# kingoftone_v2.net
KiCad netlist of a schematic drawn in EAGLE
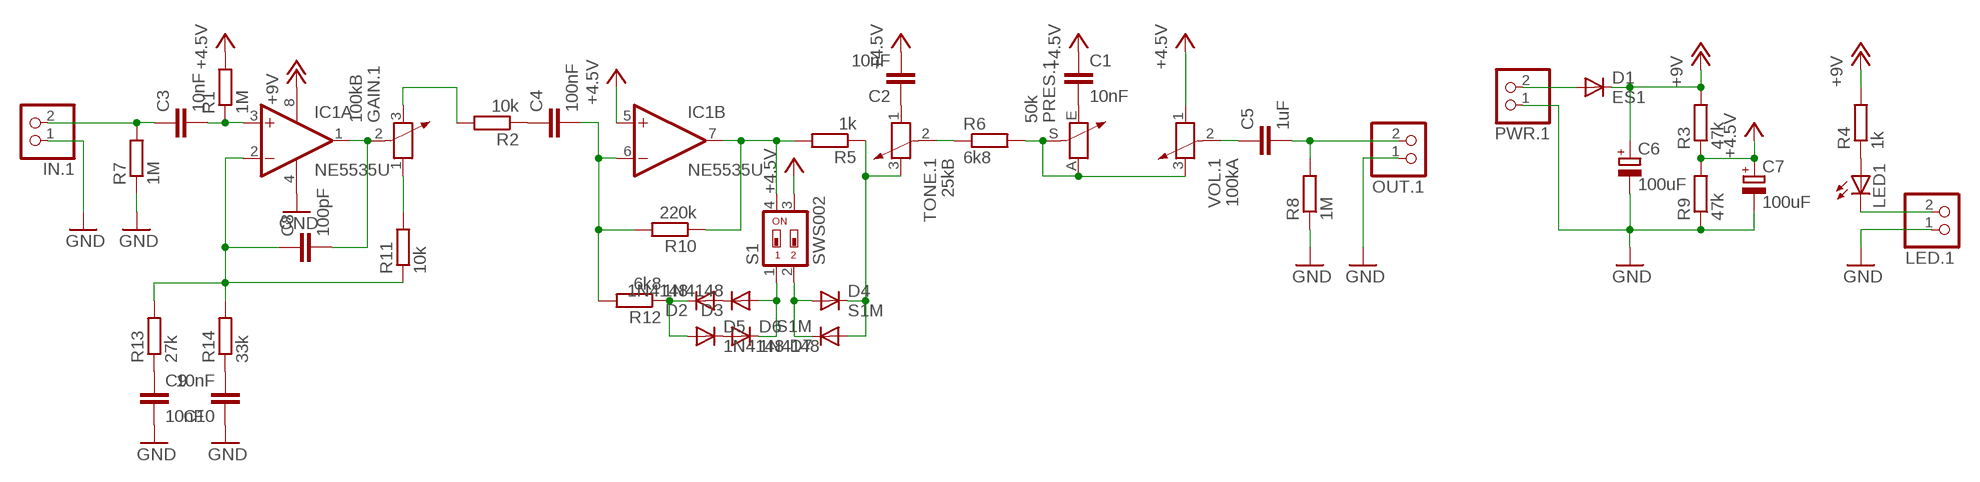
[diagram p0: schematic, sheet 1]

(export (version "E")
  (design (tool "Eeschema 10.0.6"))
  (components
    (comp (ref "C1")
      (value "10nF")
      (footprint "eagle-import:C0805K")
      (libsource (lib "eagle-import") (part "C-EUC0805K"))
    )
    (comp (ref "C2")
      (value "10nF")
      (footprint "eagle-import:C0805K")
      (libsource (lib "eagle-import") (part "C-EUC0805K"))
    )
    (comp (ref "C3")
      (value "10nF")
      (footprint "eagle-import:C0805K")
      (libsource (lib "eagle-import") (part "C-EUC0805K"))
    )
    (comp (ref "C4")
      (value "100nF")
      (footprint "eagle-import:C0805K")
      (libsource (lib "eagle-import") (part "C-EUC0805K"))
    )
    (comp (ref "C5")
      (value "1uF")
      (footprint "eagle-import:C0805K")
      (libsource (lib "eagle-import") (part "C-EUC0805K"))
    )
    (comp (ref "C6")
      (value "100uF")
      (footprint "eagle-import:PANASONIC_D")
      (libsource (lib "eagle-import") (part "CPOL-EUD"))
    )
    (comp (ref "C7")
      (value "100uF")
      (footprint "eagle-import:PANASONIC_D")
      (libsource (lib "eagle-import") (part "CPOL-EUD"))
    )
    (comp (ref "C8")
      (value "100pF")
      (footprint "eagle-import:C0805K")
      (libsource (lib "eagle-import") (part "C-EUC0805K"))
    )
    (comp (ref "C9")
      (value "10nF")
      (footprint "eagle-import:C0805K")
      (libsource (lib "eagle-import") (part "C-EUC0805K"))
    )
    (comp (ref "C10")
      (value "10nF")
      (footprint "eagle-import:C0805K")
      (libsource (lib "eagle-import") (part "C-EUC0805K"))
    )
    (comp (ref "D1")
      (value "ES1")
      (footprint "eagle-import:DO-214AC")
      (libsource (lib "eagle-import") (part "ES1"))
    )
    (comp (ref "D2")
      (value "1N4148")
      (footprint "eagle-import:D0805")
      (libsource (lib "eagle-import") (part "1N4148"))
    )
    (comp (ref "D3")
      (value "1N4148")
      (footprint "eagle-import:D0805")
      (libsource (lib "eagle-import") (part "1N4148"))
    )
    (comp (ref "D4")
      (value "S1M")
      (footprint "eagle-import:DO-214AC")
      (libsource (lib "eagle-import") (part "S1M"))
    )
    (comp (ref "D5")
      (value "1N4148")
      (footprint "eagle-import:D0805")
      (libsource (lib "eagle-import") (part "1N4148"))
    )
    (comp (ref "D6")
      (value "1N4148")
      (footprint "eagle-import:D0805")
      (libsource (lib "eagle-import") (part "1N4148"))
    )
    (comp (ref "D7")
      (value "S1M")
      (footprint "eagle-import:DO-214AC")
      (libsource (lib "eagle-import") (part "S1M"))
    )
    (comp (ref "GAIN.1")
      (value "100kB")
      (footprint "eagle-import:1X03")
      (libsource (lib "eagle-import") (part "POTENTIOMETER_"))
    )
    (comp (ref "IC1")
      (value "NE5535U")
      (footprint "eagle-import:SO08")
      (libsource (lib "eagle-import") (part "NE5535U"))
    )
    (comp (ref "IN.1")
      (value "PINHD-1X2")
      (footprint "eagle-import:1X02")
      (libsource (lib "eagle-import") (part "PINHD-1X2"))
    )
    (comp (ref "LED.1")
      (value "PINHD-1X2")
      (footprint "eagle-import:1X02")
      (libsource (lib "eagle-import") (part "PINHD-1X2"))
    )
    (comp (ref "LED1")
      (value "LED3MM")
      (footprint "eagle-import:LED3MM")
      (libsource (lib "eagle-import") (part "LED3MM"))
    )
    (comp (ref "OUT.1")
      (value "PINHD-1X2")
      (footprint "eagle-import:1X02")
      (libsource (lib "eagle-import") (part "PINHD-1X2"))
    )
    (comp (ref "PRES.1")
      (value "50k")
      (footprint "eagle-import:CT6")
      (libsource (lib "eagle-import") (part "POTENTIOMETER_CT6"))
    )
    (comp (ref "PWR.1")
      (value "PINHD-1X2")
      (footprint "eagle-import:1X02")
      (libsource (lib "eagle-import") (part "PINHD-1X2"))
    )
    (comp (ref "R1")
      (value "1M")
      (footprint "eagle-import:R0805")
      (libsource (lib "eagle-import") (part "R-EU_0805"))
    )
    (comp (ref "R2")
      (value "10k")
      (footprint "eagle-import:R0805")
      (libsource (lib "eagle-import") (part "R-EU_0805"))
    )
    (comp (ref "R3")
      (value "47k")
      (footprint "eagle-import:R0805")
      (libsource (lib "eagle-import") (part "R-EU_0805"))
    )
    (comp (ref "R4")
      (value "1k")
      (footprint "eagle-import:R0805")
      (libsource (lib "eagle-import") (part "R-EU_0805"))
    )
    (comp (ref "R5")
      (value "1k")
      (footprint "eagle-import:R0805")
      (libsource (lib "eagle-import") (part "R-EU_0805"))
    )
    (comp (ref "R6")
      (value "6k8")
      (footprint "eagle-import:R0805")
      (libsource (lib "eagle-import") (part "R-EU_0805"))
    )
    (comp (ref "R7")
      (value "1M")
      (footprint "eagle-import:R0805")
      (libsource (lib "eagle-import") (part "R-EU_0805"))
    )
    (comp (ref "R8")
      (value "1M")
      (footprint "eagle-import:R0805")
      (libsource (lib "eagle-import") (part "R-EU_0805"))
    )
    (comp (ref "R9")
      (value "47k")
      (footprint "eagle-import:R0805")
      (libsource (lib "eagle-import") (part "R-EU_0805"))
    )
    (comp (ref "R10")
      (value "220k")
      (footprint "eagle-import:R0805")
      (libsource (lib "eagle-import") (part "R-EU_0805"))
    )
    (comp (ref "R11")
      (value "10k")
      (footprint "eagle-import:R0805")
      (libsource (lib "eagle-import") (part "R-EU_0805"))
    )
    (comp (ref "R12")
      (value "6k8")
      (footprint "eagle-import:R0805")
      (libsource (lib "eagle-import") (part "R-EU_0805"))
    )
    (comp (ref "R13")
      (value "27k")
      (footprint "eagle-import:R0805")
      (libsource (lib "eagle-import") (part "R-EU_0805"))
    )
    (comp (ref "R14")
      (value "33k")
      (footprint "eagle-import:R0805")
      (libsource (lib "eagle-import") (part "R-EU_0805"))
    )
    (comp (ref "S1")
      (value "SWS002")
      (footprint "eagle-import:SMS-002")
      (libsource (lib "eagle-import") (part "SWS002"))
    )
    (comp (ref "TONE.1")
      (value "25kB")
      (footprint "eagle-import:1X03")
      (libsource (lib "eagle-import") (part "POTENTIOMETER_"))
    )
    (comp (ref "VOL.1")
      (value "100kA")
      (footprint "eagle-import:1X03")
      (libsource (lib "eagle-import") (part "POTENTIOMETER_"))
    )
  )
  (nets
    (net (code "1") (name "+4.5V") (class "Default")
      (node (ref "C1") (pin "1") (pinfunction "1_1") (pintype "passive"))
      (node (ref "C2") (pin "2") (pinfunction "2_2") (pintype "passive"))
      (node (ref "C7") (pin "+") (pinfunction "+_+") (pintype "passive"))
      (node (ref "IC1") (pin "5") (pinfunction "+IN_5") (pintype "input"))
      (node (ref "R1") (pin "2") (pinfunction "2_2") (pintype "passive"))
      (node (ref "R3") (pin "1") (pinfunction "1_1") (pintype "passive"))
      (node (ref "R9") (pin "2") (pinfunction "2_2") (pintype "passive"))
      (node (ref "S1") (pin "3") (pinfunction "3_3") (pintype "passive"))
      (node (ref "VOL.1") (pin "1") (pinfunction "1_1") (pintype "passive"))
    )
    (net (code "2") (name "+9V") (class "Default")
      (node (ref "C6") (pin "+") (pinfunction "+_+") (pintype "passive"))
      (node (ref "D1") (pin "C") (pinfunction "C_C") (pintype "passive"))
      (node (ref "IC1") (pin "8") (pinfunction "V+_8") (pintype "power_in"))
      (node (ref "R3") (pin "2") (pinfunction "2_2") (pintype "passive"))
      (node (ref "R4") (pin "2") (pinfunction "2_2") (pintype "passive"))
    )
    (net (code "3") (name "GND") (class "Default")
      (node (ref "C10") (pin "1") (pinfunction "1_1") (pintype "passive"))
      (node (ref "C6") (pin "-") (pinfunction "-_-") (pintype "passive"))
      (node (ref "C7") (pin "-") (pinfunction "-_-") (pintype "passive"))
      (node (ref "C9") (pin "2") (pinfunction "2_2") (pintype "passive"))
      (node (ref "IC1") (pin "4") (pinfunction "V-_4") (pintype "power_in"))
      (node (ref "IN.1") (pin "1") (pinfunction "1_1") (pintype "passive"))
      (node (ref "LED.1") (pin "1") (pinfunction "1_1") (pintype "passive"))
      (node (ref "OUT.1") (pin "1") (pinfunction "1_1") (pintype "passive"))
      (node (ref "PWR.1") (pin "1") (pinfunction "1_1") (pintype "passive"))
      (node (ref "R7") (pin "1") (pinfunction "1_1") (pintype "passive"))
      (node (ref "R8") (pin "1") (pinfunction "1_1") (pintype "passive"))
      (node (ref "R9") (pin "1") (pinfunction "1_1") (pintype "passive"))
    )
    (net (code "4") (name "Net-(C2-Pad1)") (class "Default")
      (node (ref "C2") (pin "1") (pinfunction "1_1") (pintype "passive"))
      (node (ref "TONE.1") (pin "1") (pinfunction "1_1") (pintype "passive"))
    )
    (net (code "5") (name "Net-(C3-Pad1)") (class "Default")
      (node (ref "C3") (pin "1") (pinfunction "1_1") (pintype "passive"))
      (node (ref "IN.1") (pin "2") (pinfunction "2_2") (pintype "passive"))
      (node (ref "R7") (pin "2") (pinfunction "2_2") (pintype "passive"))
    )
    (net (code "6") (name "Net-(C4-Pad1)") (class "Default")
      (node (ref "C4") (pin "1") (pinfunction "1_1") (pintype "passive"))
      (node (ref "R2") (pin "1") (pinfunction "1_1") (pintype "passive"))
    )
    (net (code "7") (name "Net-(C5-Pad2)") (class "Default")
      (node (ref "C5") (pin "2") (pinfunction "2_2") (pintype "passive"))
      (node (ref "OUT.1") (pin "2") (pinfunction "2_2") (pintype "passive"))
      (node (ref "R8") (pin "2") (pinfunction "2_2") (pintype "passive"))
    )
    (net (code "8") (name "Net-(C9-Pad1)") (class "Default")
      (node (ref "C9") (pin "1") (pinfunction "1_1") (pintype "passive"))
      (node (ref "R13") (pin "1") (pinfunction "1_1") (pintype "passive"))
    )
    (net (code "9") (name "Net-(C10-Pad2)") (class "Default")
      (node (ref "C10") (pin "2") (pinfunction "2_2") (pintype "passive"))
      (node (ref "R14") (pin "1") (pinfunction "1_1") (pintype "passive"))
    )
    (net (code "10") (name "Net-(D1-PadA)") (class "Default")
      (node (ref "D1") (pin "A") (pinfunction "A_A") (pintype "passive"))
      (node (ref "PWR.1") (pin "2") (pinfunction "2_2") (pintype "passive"))
    )
    (net (code "11") (name "Net-(D2-C)") (class "Default")
      (node (ref "D2") (pin "K") (pinfunction "C_K") (pintype "passive"))
      (node (ref "D5") (pin "A") (pinfunction "A_A") (pintype "passive"))
      (node (ref "R12") (pin "1") (pinfunction "1_1") (pintype "passive"))
    )
    (net (code "12") (name "Net-(D3-C)") (class "Default")
      (node (ref "D2") (pin "A") (pinfunction "A_A") (pintype "passive"))
      (node (ref "D3") (pin "K") (pinfunction "C_K") (pintype "passive"))
    )
    (net (code "13") (name "Net-(D4-PadA)") (class "Default")
      (node (ref "D4") (pin "A") (pinfunction "A_A") (pintype "passive"))
      (node (ref "D7") (pin "C") (pinfunction "C_C") (pintype "passive"))
      (node (ref "S1") (pin "2") (pinfunction "2_2") (pintype "passive"))
    )
    (net (code "14") (name "Net-(D5-C)") (class "Default")
      (node (ref "D5") (pin "K") (pinfunction "C_K") (pintype "passive"))
      (node (ref "D6") (pin "A") (pinfunction "A_A") (pintype "passive"))
    )
    (net (code "15") (name "Net-(D6-C)") (class "Default")
      (node (ref "D3") (pin "A") (pinfunction "A_A") (pintype "passive"))
      (node (ref "D6") (pin "K") (pinfunction "C_K") (pintype "passive"))
      (node (ref "S1") (pin "1") (pinfunction "1_1") (pintype "passive"))
    )
    (net (code "16") (name "Net-(GAIN.1-2)") (class "Default")
      (node (ref "GAIN.1") (pin "3") (pinfunction "2_3") (pintype "passive"))
      (node (ref "R2") (pin "2") (pinfunction "2_2") (pintype "passive"))
    )
    (net (code "17") (name "Net-(GAIN.1-3)") (class "Default")
      (node (ref "C8") (pin "2") (pinfunction "2_2") (pintype "passive"))
      (node (ref "GAIN.1") (pin "2") (pinfunction "3_2") (pintype "passive"))
      (node (ref "IC1") (pin "1") (pinfunction "OUT_1") (pintype "output"))
    )
    (net (code "18") (name "Net-(GAIN.1-Pad1)") (class "Default")
      (node (ref "GAIN.1") (pin "1") (pinfunction "1_1") (pintype "passive"))
      (node (ref "R11") (pin "2") (pinfunction "2_2") (pintype "passive"))
    )
    (net (code "19") (name "Net-(IC1A-+IN)") (class "Default")
      (node (ref "C3") (pin "2") (pinfunction "2_2") (pintype "passive"))
      (node (ref "IC1") (pin "3") (pinfunction "+IN_3") (pintype "input"))
      (node (ref "R1") (pin "1") (pinfunction "1_1") (pintype "passive"))
    )
    (net (code "20") (name "Net-(IC1A--IN)") (class "Default")
      (node (ref "C8") (pin "1") (pinfunction "1_1") (pintype "passive"))
      (node (ref "IC1") (pin "2") (pinfunction "-IN_2") (pintype "input"))
      (node (ref "R11") (pin "1") (pinfunction "1_1") (pintype "passive"))
      (node (ref "R13") (pin "2") (pinfunction "2_2") (pintype "passive"))
      (node (ref "R14") (pin "2") (pinfunction "2_2") (pintype "passive"))
    )
    (net (code "21") (name "Net-(IC1B--IN)") (class "Default")
      (node (ref "C4") (pin "2") (pinfunction "2_2") (pintype "passive"))
      (node (ref "IC1") (pin "6") (pinfunction "-IN_6") (pintype "input"))
      (node (ref "R10") (pin "2") (pinfunction "2_2") (pintype "passive"))
      (node (ref "R12") (pin "2") (pinfunction "2_2") (pintype "passive"))
    )
    (net (code "22") (name "Net-(IC1B-OUT)") (class "Default")
      (node (ref "IC1") (pin "7") (pinfunction "OUT_7") (pintype "output"))
      (node (ref "R10") (pin "1") (pinfunction "1_1") (pintype "passive"))
      (node (ref "R5") (pin "2") (pinfunction "2_2") (pintype "passive"))
      (node (ref "S1") (pin "4") (pinfunction "4_4") (pintype "passive"))
    )
    (net (code "23") (name "Net-(LED1-C)") (class "Default")
      (node (ref "LED.1") (pin "2") (pinfunction "2_2") (pintype "passive"))
      (node (ref "LED1") (pin "K") (pinfunction "C_K") (pintype "passive"))
    )
    (net (code "24") (name "Net-(LED1-PadA)") (class "Default")
      (node (ref "LED1") (pin "A") (pinfunction "A_A") (pintype "passive"))
      (node (ref "R4") (pin "1") (pinfunction "1_1") (pintype "passive"))
    )
    (net (code "25") (name "Net-(PRES.1-1)") (class "Default")
      (node (ref "PRES.1") (pin "A") (pinfunction "1_A") (pintype "passive"))
      (node (ref "PRES.1") (pin "S") (pinfunction "3_S") (pintype "passive"))
      (node (ref "R6") (pin "2") (pinfunction "2_2") (pintype "passive"))
      (node (ref "VOL.1") (pin "3") (pinfunction "2_3") (pintype "passive"))
    )
    (net (code "26") (name "Net-(PRES.1-2)") (class "Default")
      (node (ref "C1") (pin "2") (pinfunction "2_2") (pintype "passive"))
      (node (ref "PRES.1") (pin "E") (pinfunction "2_E") (pintype "passive"))
    )
    (net (code "27") (name "Net-(TONE.1-2)") (class "Default")
      (node (ref "D4") (pin "C") (pinfunction "C_C") (pintype "passive"))
      (node (ref "D7") (pin "A") (pinfunction "A_A") (pintype "passive"))
      (node (ref "R5") (pin "1") (pinfunction "1_1") (pintype "passive"))
      (node (ref "TONE.1") (pin "3") (pinfunction "2_3") (pintype "passive"))
    )
    (net (code "28") (name "Net-(TONE.1-3)") (class "Default")
      (node (ref "R6") (pin "1") (pinfunction "1_1") (pintype "passive"))
      (node (ref "TONE.1") (pin "2") (pinfunction "3_2") (pintype "passive"))
    )
    (net (code "29") (name "Net-(VOL.1-3)") (class "Default")
      (node (ref "C5") (pin "1") (pinfunction "1_1") (pintype "passive"))
      (node (ref "VOL.1") (pin "2") (pinfunction "3_2") (pintype "passive"))
    )
  )
)
